# SCS_Battery_RevA.net
KiCad netlist of a schematic drawn in Altium Designer
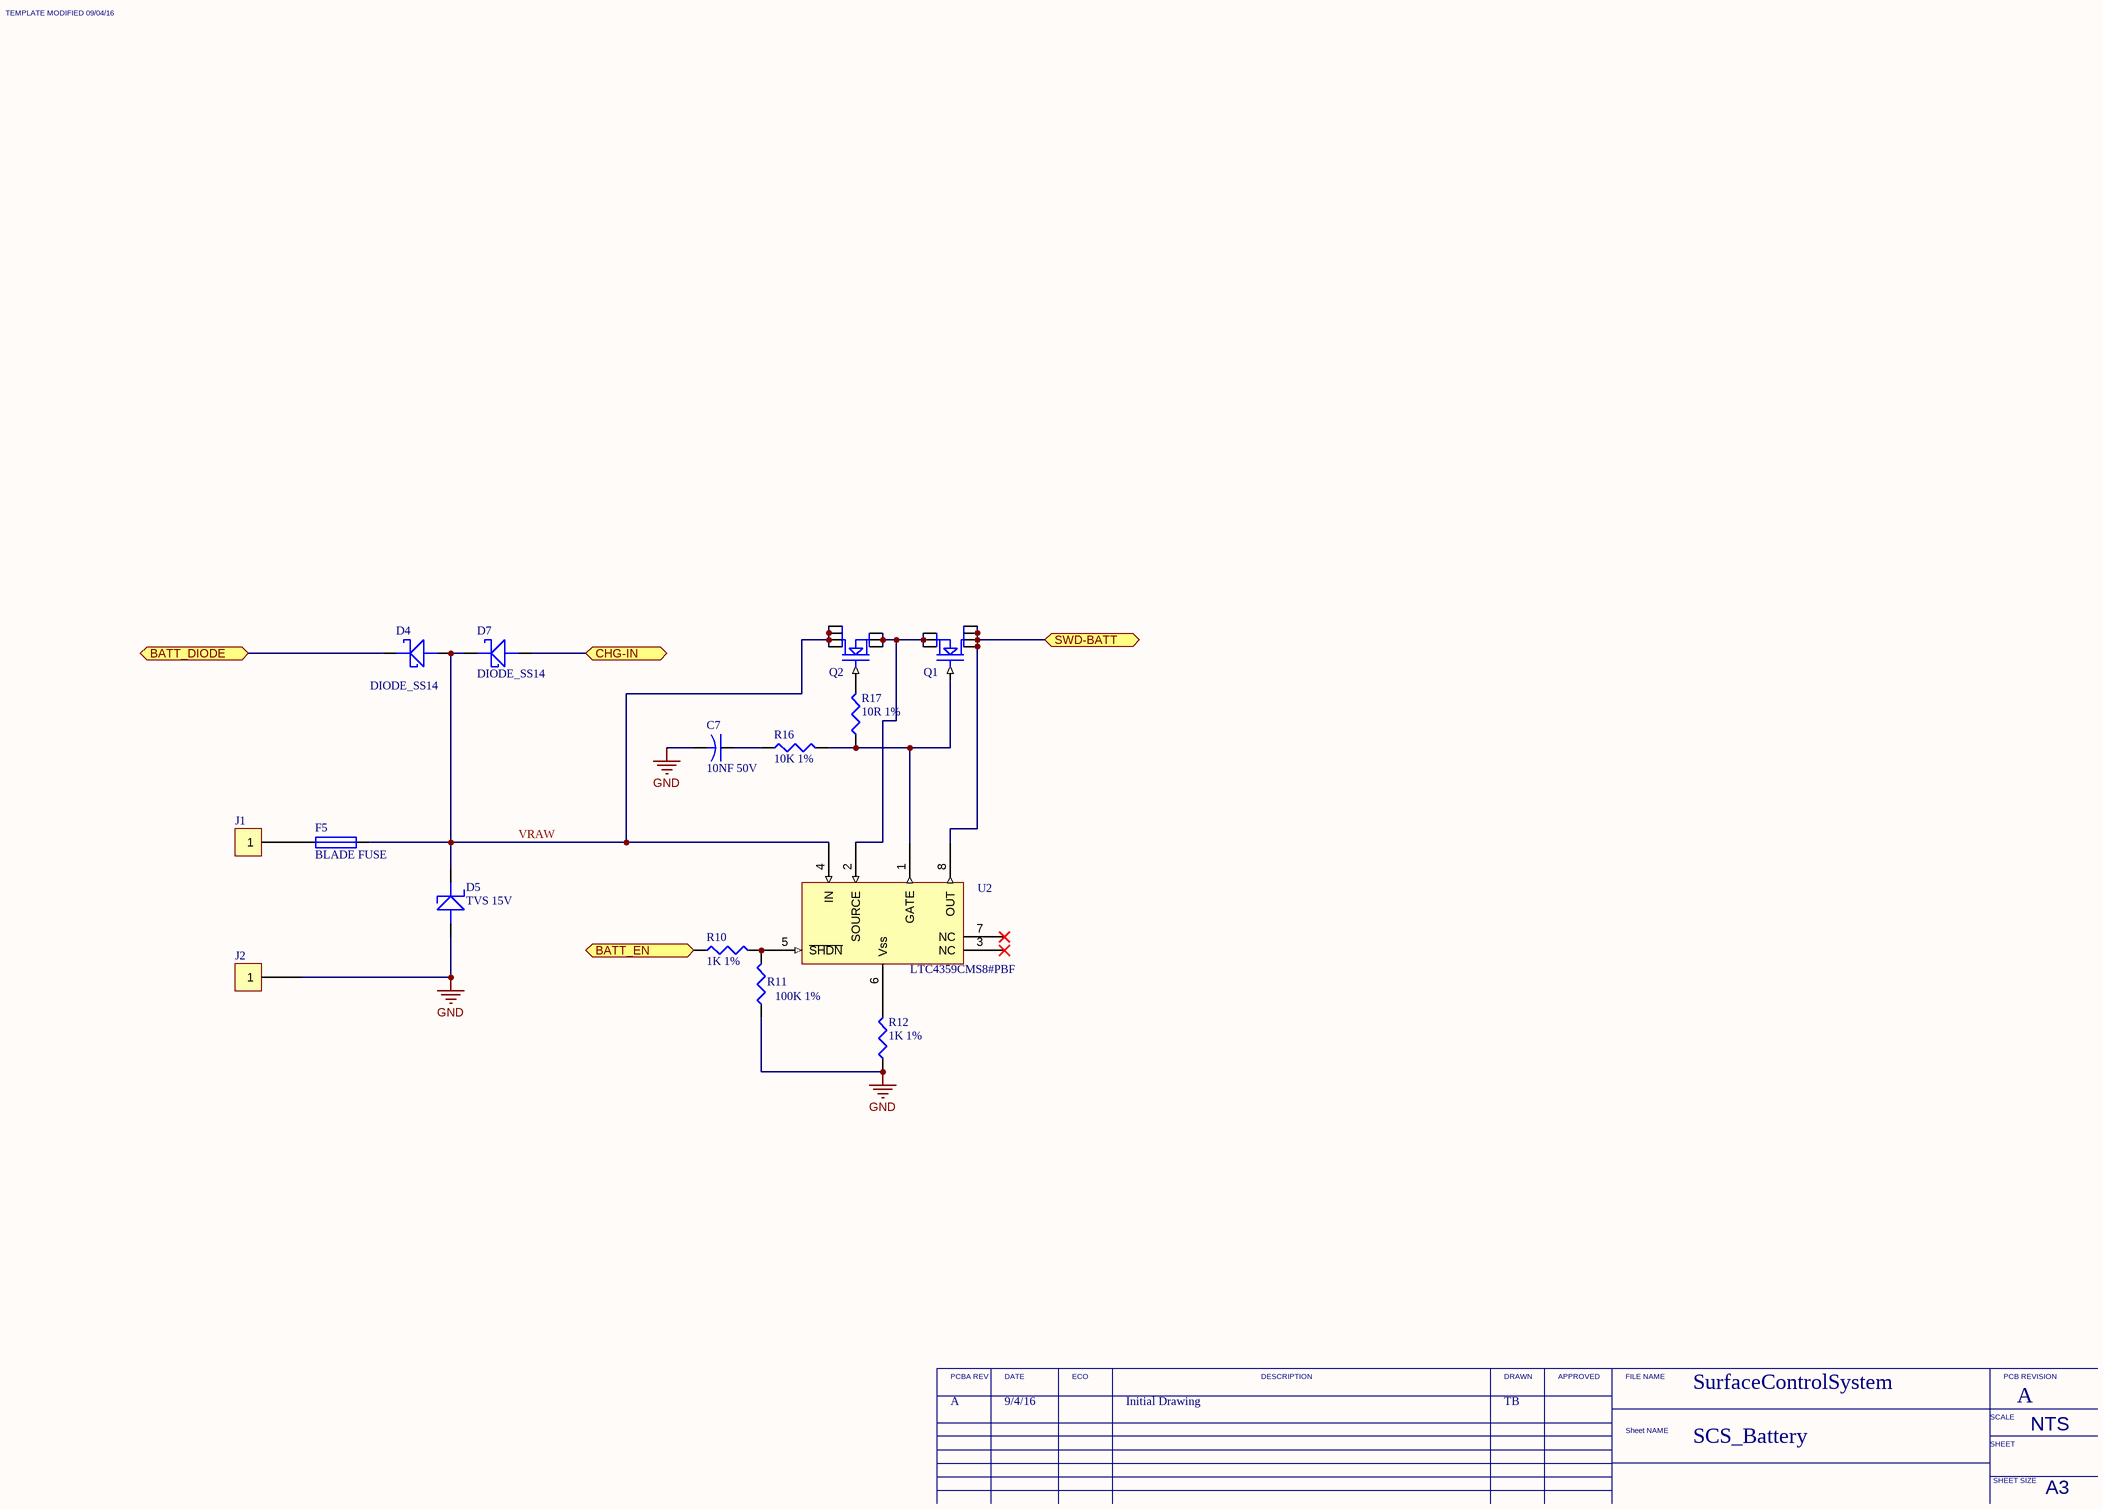
[diagram p0: SCS_Battery_RevA.SchDoc]

(export (version "E")
  (design (tool "Eeschema 10.0.6"))
  (components
    (comp (ref "C7")
      (value "10NF 50V")
      (footprint "0603")
      (description "CAP CER 10NF 50V 10% X7R 0603")
      (fields (field (name "MANUFACTURER") "Murata"))
      (libsource (lib "Caps") (part "CAP_10NF_50V_10%_0603"))
    )
    (comp (ref "D4")
      (value "DIODE_SS14")
      (footprint "DO-214AC")
      (description "Schottky Diode, 1A, 40V SS14")
      (fields (field (name "MANUFACTURER") "Fairchild"))
      (libsource (lib "PowerDistributor") (part "DIODE_SS14"))
    )
    (comp (ref "D5")
      (value "TVS 15V")
      (footprint "DO-214AB")
      (description "TVS Diode, 15V")
      (fields (field (name "MANUFACTURER") "LIttlefuse"))
      (libsource (lib "Semiconductors") (part "DIODE_TVS_SMCJ15A"))
    )
    (comp (ref "D7")
      (value "DIODE_SS14")
      (footprint "DO-214AC")
      (description "Schottky Diode, 1A, 40V SS14")
      (fields (field (name "MANUFACTURER") "Fairchild"))
      (libsource (lib "Semiconductors") (part "DIODE_SS14"))
    )
    (comp (ref "F5")
      (value "BLADE FUSE")
      (footprint "FUSEHOLDER_BLADE")
      (description "FUSE CLIP BLADE 500V 30A PCB")
      (fields (field (name "MANUFACTURER") "Keystone Electronics"))
      (libsource (lib "PowerDistributor") (part "FUSE_BLADE_500V_30A_PCB"))
    )
    (comp (ref "J1")
      (value "5mm Pitch 6.3mm SPADE")
      (footprint "CON_5mm_6.3MM_SPADE")
      (description "CON_5mm_6.3MM_SPADE")
      (fields (field (name "MANUFACTURER") "Dinkle"))
      (libsource (lib "PowerDistributor") (part "CON_5mm_6.3MM_SPADE"))
    )
    (comp (ref "J2")
      (value "5mm Pitch 6.3mm SPADE")
      (footprint "CON_5mm_6.3MM_SPADE")
      (description "CON_5mm_6.3MM_SPADE")
      (fields (field (name "MANUFACTURER") "Dinkle"))
      (libsource (lib "PowerDistributor") (part "CON_5mm_6.3MM_SPADE"))
    )
    (comp (ref "Q1")
      (value "N Channel FET")
      (footprint "SO-8")
      (description "MOSFET N-CH 30V 20A LFPAK")
      (fields (field (name "MANUFACTURER") "Alpha & Omega Semiconductor Inc."))
      (libsource (lib "Semiconductors") (part "Q_AO4578"))
    )
    (comp (ref "Q2")
      (value "N Channel FET")
      (footprint "SO-8")
      (description "MOSFET N-CH 30V 20A LFPAK")
      (fields (field (name "MANUFACTURER") "Alpha & Omega Semiconductor Inc."))
      (libsource (lib "Semiconductors") (part "Q_AO4578"))
    )
    (comp (ref "R10")
      (value "1K 1%")
      (footprint "0603")
      (description "Resistor, 1K, 1%, 0603")
      (fields (field (name "MANUFACTURER") "Bourns Inc"))
      (libsource (lib "PowerDistributor") (part "RES_1K_1%_0603"))
    )
    (comp (ref "R11")
      (value "100K 1%")
      (footprint "0603")
      (description "Resistor, 100K, 1%, 0603")
      (fields (field (name "MANUFACTURER") "Bourns Inc"))
      (libsource (lib "PowerDistributor") (part "RES_100K_1%_0603"))
    )
    (comp (ref "R12")
      (value "1K 1%")
      (footprint "0603")
      (description "Resistor, 1K, 1%, 0603")
      (fields (field (name "MANUFACTURER") "Bourns Inc"))
      (libsource (lib "PowerDistributor") (part "RES_1K_1%_0603"))
    )
    (comp (ref "R16")
      (value "10K 1%")
      (footprint "0603")
      (description "Resistor, 10K, 1%, 0603")
      (fields (field (name "MANUFACTURER") "Bourns Inc"))
      (libsource (lib "Resistors") (part "RES_10K_1%_0603"))
    )
    (comp (ref "R17")
      (value "10R 1%")
      (footprint "0603")
      (description "Resistor, 10R, 1%, 0603")
      (fields (field (name "MANUFACTURER") "Bourns Inc"))
      (libsource (lib "Resistors") (part "RES_10R_1%_0603"))
    )
    (comp (ref "U2")
      (value "LTC4359CMS8#PBF")
      (footprint "TSOP65P490X110-8M")
      (description "Ideal Diode Controller")
      (fields (field (name "MANUFACTURER") "Linear Technology"))
      (libsource (lib "PowerDistributor") (part "IC_LTC4359"))
    )
  )
  (nets
    (net (code "1") (name "/BATT_DIODE") (class "Default")
      (node (ref "D4") (pin "K") (pinfunction "K_K") (pintype "passive"))
    )
    (net (code "2") (name "/BATT_EN") (class "Default") (node (ref "R10") (pin "1") (pintype "passive")))
    (net (code "3") (name "/CHG-IN") (class "Default")
      (node (ref "D7") (pin "A") (pinfunction "A_A") (pintype "passive"))
    )
    (net (code "4") (name "/SWD-BATT") (class "Default")
      (node (ref "Q1") (pin "5") (pinfunction "DRAIN_5") (pintype "power_in"))
      (node (ref "Q1") (pin "6") (pinfunction "DRAIN_6") (pintype "power_in"))
      (node (ref "Q1") (pin "7") (pinfunction "DRAIN_7") (pintype "power_in"))
      (node (ref "Q1") (pin "8") (pinfunction "DRAIN_8") (pintype "power_in"))
      (node (ref "U2") (pin "8") (pinfunction "OUT_8") (pintype "output"))
    )
    (net (code "5") (name "/VRAW") (class "Default")
      (node (ref "D4") (pin "A") (pinfunction "A_A") (pintype "passive"))
      (node (ref "D5") (pin "K") (pinfunction "K_K") (pintype "passive"))
      (node (ref "D7") (pin "K") (pinfunction "K_K") (pintype "passive"))
      (node (ref "F5") (pin "2") (pintype "passive"))
      (node (ref "Q2") (pin "5") (pinfunction "DRAIN_5") (pintype "power_in"))
      (node (ref "Q2") (pin "6") (pinfunction "DRAIN_6") (pintype "power_in"))
      (node (ref "Q2") (pin "7") (pinfunction "DRAIN_7") (pintype "power_in"))
      (node (ref "Q2") (pin "8") (pinfunction "DRAIN_8") (pintype "power_in"))
      (node (ref "U2") (pin "4") (pinfunction "IN_4") (pintype "input"))
    )
    (net (code "6") (name "GND") (class "Default")
      (node (ref "C7") (pin "2") (pinfunction "2_2") (pintype "passive"))
      (node (ref "D5") (pin "A") (pinfunction "A_A") (pintype "passive"))
      (node (ref "J2") (pin "1") (pinfunction "1_1") (pintype "power_in"))
      (node (ref "R11") (pin "1") (pintype "passive"))
      (node (ref "R12") (pin "1") (pintype "passive"))
    )
    (net (code "7") (name "Net-(C7-Pad1)") (class "Default")
      (node (ref "C7") (pin "1") (pinfunction "1_1") (pintype "passive"))
      (node (ref "R16") (pin "1") (pintype "passive"))
    )
    (net (code "8") (name "Net-(F5-Pad1)") (class "Default")
      (node (ref "F5") (pin "1") (pintype "passive"))
      (node (ref "J1") (pin "1") (pinfunction "1_1") (pintype "power_in"))
    )
    (net (code "9") (name "Net-(Q1-GATE)") (class "Default")
      (node (ref "Q1") (pin "4") (pinfunction "GATE_4") (pintype "input"))
      (node (ref "R16") (pin "2") (pintype "passive"))
      (node (ref "R17") (pin "1") (pintype "passive"))
      (node (ref "U2") (pin "1") (pinfunction "GATE_1") (pintype "output"))
    )
    (net (code "10") (name "Net-(Q2-GATE)") (class "Default")
      (node (ref "Q2") (pin "4") (pinfunction "GATE_4") (pintype "input"))
      (node (ref "R17") (pin "2") (pintype "passive"))
    )
    (net (code "11") (name "Net-(U2-SOURCE)") (class "Default")
      (node (ref "Q1") (pin "1") (pinfunction "SOURCE_1") (pintype "power_in"))
      (node (ref "Q1") (pin "2") (pinfunction "SOURCE_2") (pintype "power_in"))
      (node (ref "Q1") (pin "3") (pinfunction "SOURCE_3") (pintype "power_in"))
      (node (ref "Q2") (pin "1") (pinfunction "SOURCE_1") (pintype "power_in"))
      (node (ref "Q2") (pin "2") (pinfunction "SOURCE_2") (pintype "power_in"))
      (node (ref "Q2") (pin "3") (pinfunction "SOURCE_3") (pintype "power_in"))
      (node (ref "U2") (pin "2") (pinfunction "SOURCE_2") (pintype "input"))
    )
    (net (code "12") (name "Net-(U2-Vss)") (class "Default")
      (node (ref "R12") (pin "2") (pintype "passive"))
      (node (ref "U2") (pin "6") (pinfunction "Vss_6") (pintype "power_in"))
    )
    (net (code "13") (name "Net-(U2-~{SHDN})") (class "Default")
      (node (ref "R10") (pin "2") (pintype "passive"))
      (node (ref "R11") (pin "2") (pintype "passive"))
      (node (ref "U2") (pin "5") (pinfunction "~{SHDN}_5") (pintype "input"))
    )
    (net (code "14") (name "unconnected-(U2-NC-Pad3)") (class "Default")
      (node (ref "U2") (pin "3") (pinfunction "NC_3") (pintype "tri_state+no_connect"))
    )
    (net (code "15") (name "unconnected-(U2-NC-Pad7)") (class "Default")
      (node (ref "U2") (pin "7") (pinfunction "NC_7") (pintype "tri_state+no_connect"))
    )
  )
)
